# adc.net
KiCad netlist of a schematic drawn in Altium Designer
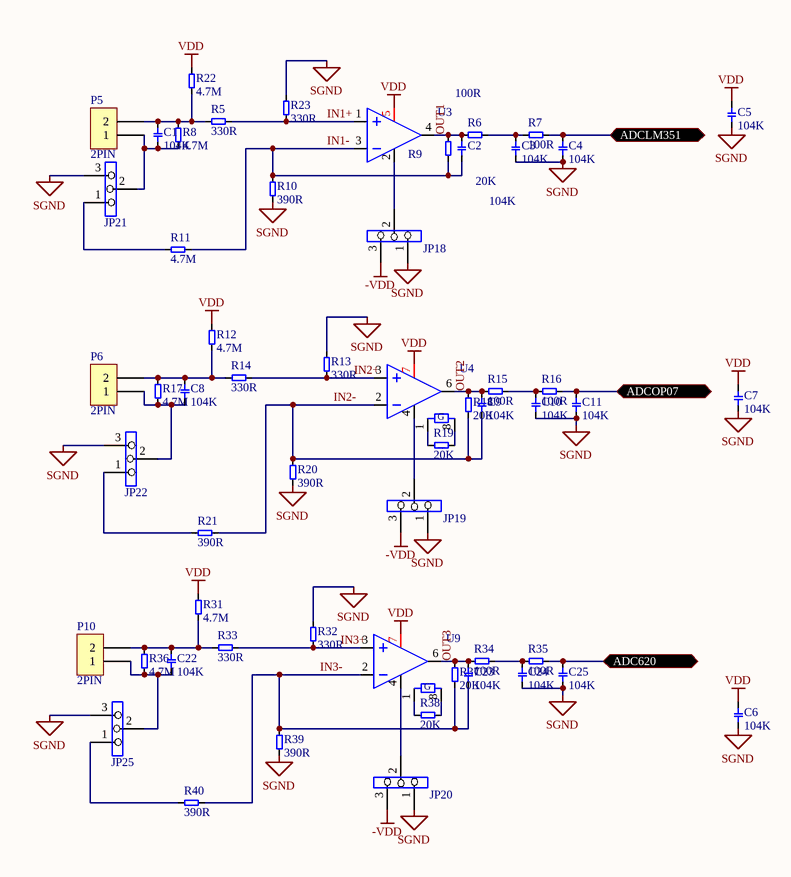
[diagram p0: adc.SchDoc]

(export (version "E")
  (design (tool "Eeschema 10.0.6"))
  (components
    (comp (ref "C1")
      (value "104K")
      (footprint "0603")
      (description "电容")
      (fields (field (name "PUBLISHER") "Altium Limited"))
      (libsource (lib "Miscellaneous Devices") (part "Cap"))
    )
    (comp (ref "C2")
      (value "104K")
      (footprint "0603")
      (description "电容")
      (fields (field (name "PUBLISHER") "Altium Limited"))
      (libsource (lib "Miscellaneous Devices") (part "Cap"))
    )
    (comp (ref "C3")
      (value "104K")
      (footprint "0603")
      (description "电容")
      (fields (field (name "PUBLISHER") "Altium Limited"))
      (libsource (lib "Miscellaneous Devices") (part "Cap"))
    )
    (comp (ref "C4")
      (value "104K")
      (footprint "0603")
      (description "电容")
      (fields (field (name "PUBLISHER") "Altium Limited"))
      (libsource (lib "Miscellaneous Devices") (part "Cap"))
    )
    (comp (ref "C5")
      (value "104K")
      (footprint "0603")
      (description "电容")
      (fields (field (name "PUBLISHER") "Altium Limited"))
      (libsource (lib "Miscellaneous Devices") (part "Cap"))
    )
    (comp (ref "C6")
      (value "104K")
      (footprint "0603")
      (description "电容")
      (fields (field (name "PUBLISHER") "Altium Limited"))
      (libsource (lib "Miscellaneous Devices") (part "Cap"))
    )
    (comp (ref "C7")
      (value "104K")
      (footprint "0603")
      (description "电容")
      (fields (field (name "PUBLISHER") "Altium Limited"))
      (libsource (lib "Miscellaneous Devices") (part "Cap"))
    )
    (comp (ref "C8")
      (value "104K")
      (footprint "0603")
      (description "电容")
      (fields (field (name "PUBLISHER") "Altium Limited"))
      (libsource (lib "Miscellaneous Devices") (part "Cap"))
    )
    (comp (ref "C9")
      (value "104K")
      (footprint "0603")
      (description "电容")
      (fields (field (name "PUBLISHER") "Altium Limited"))
      (libsource (lib "Miscellaneous Devices") (part "Cap"))
    )
    (comp (ref "C10")
      (value "104K")
      (footprint "0603")
      (description "电容")
      (fields (field (name "PUBLISHER") "Altium Limited"))
      (libsource (lib "Miscellaneous Devices") (part "Cap"))
    )
    (comp (ref "C11")
      (value "104K")
      (footprint "0603")
      (description "电容")
      (fields (field (name "PUBLISHER") "Altium Limited"))
      (libsource (lib "Miscellaneous Devices") (part "Cap"))
    )
    (comp (ref "C22")
      (value "104K")
      (footprint "0603")
      (description "电容")
      (fields (field (name "PUBLISHER") "Altium Limited"))
      (libsource (lib "Miscellaneous Devices") (part "Cap"))
    )
    (comp (ref "C23")
      (value "104K")
      (footprint "0603")
      (description "电容")
      (fields (field (name "PUBLISHER") "Altium Limited"))
      (libsource (lib "Miscellaneous Devices") (part "Cap"))
    )
    (comp (ref "C24")
      (value "104K")
      (footprint "0603")
      (description "电容")
      (fields (field (name "PUBLISHER") "Altium Limited"))
      (libsource (lib "Miscellaneous Devices") (part "Cap"))
    )
    (comp (ref "C25")
      (value "104K")
      (footprint "0603")
      (description "电容")
      (fields (field (name "PUBLISHER") "Altium Limited"))
      (libsource (lib "Miscellaneous Devices") (part "Cap"))
    )
    (comp (ref "JP18")
      (value "Jumper3")
      (footprint "CON3-P2.54")
      (libsource (lib "Miscellaneous Connectors") (part "Jumper3"))
    )
    (comp (ref "JP19")
      (value "Jumper3")
      (footprint "CON3-P2.54")
      (libsource (lib "Miscellaneous Connectors") (part "Jumper3"))
    )
    (comp (ref "JP20")
      (value "Jumper3")
      (footprint "CON3-P2.54")
      (libsource (lib "Miscellaneous Connectors") (part "Jumper3"))
    )
    (comp (ref "JP21")
      (value "Jumper3")
      (footprint "CON3-P2.54")
      (libsource (lib "Miscellaneous Connectors") (part "Jumper3"))
    )
    (comp (ref "JP22")
      (value "Jumper3")
      (footprint "CON3-P2.54")
      (libsource (lib "Miscellaneous Connectors") (part "Jumper3"))
    )
    (comp (ref "JP25")
      (value "Jumper3")
      (footprint "CON3-P2.54")
      (libsource (lib "Miscellaneous Connectors") (part "Jumper3"))
    )
    (comp (ref "P5")
      (value "2PIN")
      (footprint "CON2-P2.54")
      (description "连接器")
      (fields (field (name "PUBLISHER") "Altium Limited"))
      (libsource (lib "Miscellaneous Connectors") (part "Header 2"))
    )
    (comp (ref "P6")
      (value "2PIN")
      (footprint "CON2-P2.54")
      (description "连接器")
      (fields (field (name "PUBLISHER") "Altium Limited"))
      (libsource (lib "Miscellaneous Connectors") (part "Header 2"))
    )
    (comp (ref "P10")
      (value "2PIN")
      (footprint "CON2-P2.54")
      (description "连接器")
      (fields (field (name "PUBLISHER") "Altium Limited"))
      (libsource (lib "Miscellaneous Connectors") (part "Header 2"))
    )
    (comp (ref "R5")
      (value "330R")
      (footprint "0603")
      (description "电阻")
      (fields (field (name "PUBLISHER") "Altium Limited"))
      (libsource (lib "Miscellaneous Devices") (part "Res1"))
    )
    (comp (ref "R6")
      (value "100R")
      (footprint "0603")
      (description "电阻")
      (fields (field (name "PUBLISHER") "Altium Limited"))
      (libsource (lib "Miscellaneous Devices") (part "Res1"))
    )
    (comp (ref "R7")
      (value "100R")
      (footprint "0603")
      (description "电阻")
      (fields (field (name "PUBLISHER") "Altium Limited"))
      (libsource (lib "Miscellaneous Devices") (part "Res1"))
    )
    (comp (ref "R8")
      (value "4.7M")
      (footprint "0603")
      (description "电阻")
      (fields (field (name "PUBLISHER") "Altium Limited"))
      (libsource (lib "Miscellaneous Devices") (part "Res1"))
    )
    (comp (ref "R9")
      (value "20K")
      (footprint "0603")
      (description "电阻")
      (fields (field (name "PUBLISHER") "Altium Limited"))
      (libsource (lib "Miscellaneous Devices") (part "Res1"))
    )
    (comp (ref "R10")
      (value "390R")
      (footprint "0603")
      (description "电阻")
      (fields (field (name "PUBLISHER") "Altium Limited"))
      (libsource (lib "Miscellaneous Devices") (part "Res1"))
    )
    (comp (ref "R11")
      (value "4.7M")
      (footprint "0603")
      (description "电阻")
      (fields (field (name "PUBLISHER") "Altium Limited"))
      (libsource (lib "Miscellaneous Devices") (part "Res1"))
    )
    (comp (ref "R12")
      (value "4.7M")
      (footprint "0603")
      (description "电阻")
      (fields (field (name "PUBLISHER") "Altium Limited"))
      (libsource (lib "Miscellaneous Devices") (part "Res1"))
    )
    (comp (ref "R13")
      (value "330R")
      (footprint "0603")
      (description "电阻")
      (fields (field (name "PUBLISHER") "Altium Limited"))
      (libsource (lib "Miscellaneous Devices") (part "Res1"))
    )
    (comp (ref "R14")
      (value "330R")
      (footprint "0603")
      (description "电阻")
      (fields (field (name "PUBLISHER") "Altium Limited"))
      (libsource (lib "Miscellaneous Devices") (part "Res1"))
    )
    (comp (ref "R15")
      (value "100R")
      (footprint "0603")
      (description "电阻")
      (fields (field (name "PUBLISHER") "Altium Limited"))
      (libsource (lib "Miscellaneous Devices") (part "Res1"))
    )
    (comp (ref "R16")
      (value "100R")
      (footprint "0603")
      (description "电阻")
      (fields (field (name "PUBLISHER") "Altium Limited"))
      (libsource (lib "Miscellaneous Devices") (part "Res1"))
    )
    (comp (ref "R17")
      (value "4.7M")
      (footprint "0603")
      (description "电阻")
      (fields (field (name "PUBLISHER") "Altium Limited"))
      (libsource (lib "Miscellaneous Devices") (part "Res1"))
    )
    (comp (ref "R18")
      (value "20K")
      (footprint "0603")
      (description "电阻")
      (fields (field (name "PUBLISHER") "Altium Limited"))
      (libsource (lib "Miscellaneous Devices") (part "Res1"))
    )
    (comp (ref "R19")
      (value "20K")
      (footprint "0603")
      (description "电阻")
      (fields (field (name "PUBLISHER") "Altium Limited"))
      (libsource (lib "Miscellaneous Devices") (part "Res1"))
    )
    (comp (ref "R20")
      (value "390R")
      (footprint "0603")
      (description "电阻")
      (fields (field (name "PUBLISHER") "Altium Limited"))
      (libsource (lib "Miscellaneous Devices") (part "Res1"))
    )
    (comp (ref "R21")
      (value "390R")
      (footprint "0603")
      (description "电阻")
      (fields (field (name "PUBLISHER") "Altium Limited"))
      (libsource (lib "Miscellaneous Devices") (part "Res1"))
    )
    (comp (ref "R22")
      (value "4.7M")
      (footprint "0603")
      (description "电阻")
      (fields (field (name "PUBLISHER") "Altium Limited"))
      (libsource (lib "Miscellaneous Devices") (part "Res1"))
    )
    (comp (ref "R23")
      (value "330R")
      (footprint "0603")
      (description "电阻")
      (fields (field (name "PUBLISHER") "Altium Limited"))
      (libsource (lib "Miscellaneous Devices") (part "Res1"))
    )
    (comp (ref "R31")
      (value "4.7M")
      (footprint "0603")
      (description "电阻")
      (fields (field (name "PUBLISHER") "Altium Limited"))
      (libsource (lib "Miscellaneous Devices") (part "Res1"))
    )
    (comp (ref "R32")
      (value "330R")
      (footprint "0603")
      (description "电阻")
      (fields (field (name "PUBLISHER") "Altium Limited"))
      (libsource (lib "Miscellaneous Devices") (part "Res1"))
    )
    (comp (ref "R33")
      (value "330R")
      (footprint "0603")
      (description "电阻")
      (fields (field (name "PUBLISHER") "Altium Limited"))
      (libsource (lib "Miscellaneous Devices") (part "Res1"))
    )
    (comp (ref "R34")
      (value "100R")
      (footprint "0603")
      (description "电阻")
      (fields (field (name "PUBLISHER") "Altium Limited"))
      (libsource (lib "Miscellaneous Devices") (part "Res1"))
    )
    (comp (ref "R35")
      (value "100R")
      (footprint "0603")
      (description "电阻")
      (fields (field (name "PUBLISHER") "Altium Limited"))
      (libsource (lib "Miscellaneous Devices") (part "Res1"))
    )
    (comp (ref "R36")
      (value "4.7M")
      (footprint "0603")
      (description "电阻")
      (fields (field (name "PUBLISHER") "Altium Limited"))
      (libsource (lib "Miscellaneous Devices") (part "Res1"))
    )
    (comp (ref "R37")
      (value "20K")
      (footprint "0603")
      (description "电阻")
      (fields (field (name "PUBLISHER") "Altium Limited"))
      (libsource (lib "Miscellaneous Devices") (part "Res1"))
    )
    (comp (ref "R38")
      (value "20K")
      (footprint "0603")
      (description "电阻")
      (fields (field (name "PUBLISHER") "Altium Limited"))
      (libsource (lib "Miscellaneous Devices") (part "Res1"))
    )
    (comp (ref "R39")
      (value "390R")
      (footprint "0603")
      (description "电阻")
      (fields (field (name "PUBLISHER") "Altium Limited"))
      (libsource (lib "Miscellaneous Devices") (part "Res1"))
    )
    (comp (ref "R40")
      (value "390R")
      (footprint "0603")
      (description "电阻")
      (fields (field (name "PUBLISHER") "Altium Limited"))
      (libsource (lib "Miscellaneous Devices") (part "Res1"))
    )
    (comp (ref "U3")
      (value "LM321")
      (footprint "SOT-23-5L")
      (description "运放")
      (libsource (lib "Miscellaneous Devices") (part "LM321"))
    )
    (comp (ref "U4")
      (value "OP07")
      (footprint "SOIC8_39MM")
      (description "运放")
      (libsource (lib "Miscellaneous Devices") (part "AD620"))
    )
    (comp (ref "U9")
      (value "OP07")
      (footprint "SOIC8_39MM")
      (description "运放")
      (libsource (lib "Miscellaneous Devices") (part "AD620"))
    )
  )
  (nets
    (net (code "1") (name "-VDD") (class "Default")
      (node (ref "JP18") (pin "3") (pintype "passive"))
      (node (ref "JP19") (pin "3") (pintype "passive"))
      (node (ref "JP20") (pin "3") (pintype "passive"))
    )
    (net (code "2") (name "/ADC620") (class "Default")
      (node (ref "C25") (pin "2") (pinfunction "2_2") (pintype "passive"))
      (node (ref "R35") (pin "1") (pinfunction "1_1") (pintype "passive"))
    )
    (net (code "3") (name "/ADCLM351") (class "Default")
      (node (ref "C4") (pin "2") (pinfunction "2_2") (pintype "passive"))
      (node (ref "R7") (pin "1") (pinfunction "1_1") (pintype "passive"))
    )
    (net (code "4") (name "/ADCOP07") (class "Default")
      (node (ref "C11") (pin "2") (pinfunction "2_2") (pintype "passive"))
      (node (ref "R16") (pin "1") (pinfunction "1_1") (pintype "passive"))
    )
    (net (code "5") (name "/IN1+") (class "Default")
      (node (ref "R23") (pin "1") (pinfunction "1_1") (pintype "passive"))
      (node (ref "R5") (pin "2") (pinfunction "2_2") (pintype "passive"))
      (node (ref "U3") (pin "1") (pinfunction "IN1+_1") (pintype "passive"))
    )
    (net (code "6") (name "/IN1-") (class "Default")
      (node (ref "C2") (pin "1") (pinfunction "1_1") (pintype "passive"))
      (node (ref "R10") (pin "1") (pinfunction "1_1") (pintype "passive"))
      (node (ref "R11") (pin "1") (pinfunction "1_1") (pintype "passive"))
      (node (ref "R9") (pin "2") (pinfunction "2_2") (pintype "passive"))
      (node (ref "U3") (pin "3") (pinfunction "IN1-_3") (pintype "passive"))
    )
    (net (code "7") (name "/IN2+") (class "Default")
      (node (ref "R13") (pin "1") (pinfunction "1_1") (pintype "passive"))
      (node (ref "R14") (pin "2") (pinfunction "2_2") (pintype "passive"))
      (node (ref "U4") (pin "3") (pinfunction "IN1+_3") (pintype "passive"))
    )
    (net (code "8") (name "/IN2-") (class "Default")
      (node (ref "C9") (pin "1") (pinfunction "1_1") (pintype "passive"))
      (node (ref "R18") (pin "2") (pinfunction "2_2") (pintype "passive"))
      (node (ref "R20") (pin "1") (pinfunction "1_1") (pintype "passive"))
      (node (ref "R21") (pin "2") (pinfunction "2_2") (pintype "passive"))
      (node (ref "U4") (pin "2") (pinfunction "IN1-_2") (pintype "passive"))
    )
    (net (code "9") (name "/IN3+") (class "Default")
      (node (ref "R32") (pin "1") (pinfunction "1_1") (pintype "passive"))
      (node (ref "R33") (pin "2") (pinfunction "2_2") (pintype "passive"))
      (node (ref "U9") (pin "3") (pinfunction "IN1+_3") (pintype "passive"))
    )
    (net (code "10") (name "/IN3-") (class "Default")
      (node (ref "C23") (pin "1") (pinfunction "1_1") (pintype "passive"))
      (node (ref "R37") (pin "2") (pinfunction "2_2") (pintype "passive"))
      (node (ref "R39") (pin "1") (pinfunction "1_1") (pintype "passive"))
      (node (ref "R40") (pin "2") (pinfunction "2_2") (pintype "passive"))
      (node (ref "U9") (pin "2") (pinfunction "IN1-_2") (pintype "passive"))
    )
    (net (code "11") (name "/OUT1") (class "Default")
      (node (ref "C2") (pin "2") (pinfunction "2_2") (pintype "passive"))
      (node (ref "R6") (pin "2") (pinfunction "2_2") (pintype "passive"))
      (node (ref "R9") (pin "1") (pinfunction "1_1") (pintype "passive"))
      (node (ref "U3") (pin "4") (pinfunction "OUT1_4") (pintype "passive"))
    )
    (net (code "12") (name "/OUT2") (class "Default")
      (node (ref "C9") (pin "2") (pinfunction "2_2") (pintype "passive"))
      (node (ref "R15") (pin "2") (pinfunction "2_2") (pintype "passive"))
      (node (ref "R18") (pin "1") (pinfunction "1_1") (pintype "passive"))
      (node (ref "U4") (pin "6") (pinfunction "OUT1_6") (pintype "passive"))
    )
    (net (code "13") (name "/OUT3") (class "Default")
      (node (ref "C23") (pin "2") (pinfunction "2_2") (pintype "passive"))
      (node (ref "R34") (pin "2") (pinfunction "2_2") (pintype "passive"))
      (node (ref "R37") (pin "1") (pinfunction "1_1") (pintype "passive"))
      (node (ref "U9") (pin "6") (pinfunction "OUT1_6") (pintype "passive"))
    )
    (net (code "14") (name "Net-(C1-Pad1)") (class "Default")
      (node (ref "C1") (pin "1") (pinfunction "1_1") (pintype "passive"))
      (node (ref "JP21") (pin "2") (pintype "passive"))
      (node (ref "P5") (pin "1") (pinfunction "1_1") (pintype "passive"))
      (node (ref "R8") (pin "2") (pinfunction "2_2") (pintype "passive"))
    )
    (net (code "15") (name "Net-(C1-Pad2)") (class "Default")
      (node (ref "C1") (pin "2") (pinfunction "2_2") (pintype "passive"))
      (node (ref "P5") (pin "2") (pinfunction "2_2") (pintype "passive"))
      (node (ref "R22") (pin "2") (pinfunction "2_2") (pintype "passive"))
      (node (ref "R5") (pin "1") (pinfunction "1_1") (pintype "passive"))
      (node (ref "R8") (pin "1") (pinfunction "1_1") (pintype "passive"))
    )
    (net (code "16") (name "Net-(C3-Pad2)") (class "Default")
      (node (ref "C3") (pin "2") (pinfunction "2_2") (pintype "passive"))
      (node (ref "R6") (pin "1") (pinfunction "1_1") (pintype "passive"))
      (node (ref "R7") (pin "2") (pinfunction "2_2") (pintype "passive"))
    )
    (net (code "17") (name "Net-(C8-Pad1)") (class "Default")
      (node (ref "C8") (pin "1") (pinfunction "1_1") (pintype "passive"))
      (node (ref "JP22") (pin "2") (pintype "passive"))
      (node (ref "P6") (pin "1") (pinfunction "1_1") (pintype "passive"))
      (node (ref "R17") (pin "2") (pinfunction "2_2") (pintype "passive"))
    )
    (net (code "18") (name "Net-(C8-Pad2)") (class "Default")
      (node (ref "C8") (pin "2") (pinfunction "2_2") (pintype "passive"))
      (node (ref "P6") (pin "2") (pinfunction "2_2") (pintype "passive"))
      (node (ref "R12") (pin "2") (pinfunction "2_2") (pintype "passive"))
      (node (ref "R14") (pin "1") (pinfunction "1_1") (pintype "passive"))
      (node (ref "R17") (pin "1") (pinfunction "1_1") (pintype "passive"))
    )
    (net (code "19") (name "Net-(C10-Pad2)") (class "Default")
      (node (ref "C10") (pin "2") (pinfunction "2_2") (pintype "passive"))
      (node (ref "R15") (pin "1") (pinfunction "1_1") (pintype "passive"))
      (node (ref "R16") (pin "2") (pinfunction "2_2") (pintype "passive"))
    )
    (net (code "20") (name "Net-(C22-Pad1)") (class "Default")
      (node (ref "C22") (pin "1") (pinfunction "1_1") (pintype "passive"))
      (node (ref "JP25") (pin "2") (pintype "passive"))
      (node (ref "P10") (pin "1") (pinfunction "1_1") (pintype "passive"))
      (node (ref "R36") (pin "2") (pinfunction "2_2") (pintype "passive"))
    )
    (net (code "21") (name "Net-(C22-Pad2)") (class "Default")
      (node (ref "C22") (pin "2") (pinfunction "2_2") (pintype "passive"))
      (node (ref "P10") (pin "2") (pinfunction "2_2") (pintype "passive"))
      (node (ref "R31") (pin "2") (pinfunction "2_2") (pintype "passive"))
      (node (ref "R33") (pin "1") (pinfunction "1_1") (pintype "passive"))
      (node (ref "R36") (pin "1") (pinfunction "1_1") (pintype "passive"))
    )
    (net (code "22") (name "Net-(C24-Pad2)") (class "Default")
      (node (ref "C24") (pin "2") (pinfunction "2_2") (pintype "passive"))
      (node (ref "R34") (pin "1") (pinfunction "1_1") (pintype "passive"))
      (node (ref "R35") (pin "2") (pinfunction "2_2") (pintype "passive"))
    )
    (net (code "23") (name "Net-(JP21-Pad1)") (class "Default")
      (node (ref "JP21") (pin "1") (pintype "passive"))
      (node (ref "R11") (pin "2") (pinfunction "2_2") (pintype "passive"))
    )
    (net (code "24") (name "Net-(JP22-Pad1)") (class "Default")
      (node (ref "JP22") (pin "1") (pintype "passive"))
      (node (ref "R21") (pin "1") (pinfunction "1_1") (pintype "passive"))
    )
    (net (code "25") (name "Net-(JP25-Pad1)") (class "Default")
      (node (ref "JP25") (pin "1") (pintype "passive"))
      (node (ref "R40") (pin "1") (pinfunction "1_1") (pintype "passive"))
    )
    (net (code "26") (name "Net-(R19-Pad1)") (class "Default")
      (node (ref "R19") (pin "1") (pinfunction "1_1") (pintype "passive"))
      (node (ref "U4") (pin "1") (pinfunction "RG_1") (pintype "passive"))
    )
    (net (code "27") (name "Net-(R19-Pad2)") (class "Default")
      (node (ref "R19") (pin "2") (pinfunction "2_2") (pintype "passive"))
      (node (ref "U4") (pin "8") (pinfunction "RG_8") (pintype "passive"))
    )
    (net (code "28") (name "Net-(R38-Pad1)") (class "Default")
      (node (ref "R38") (pin "1") (pinfunction "1_1") (pintype "passive"))
      (node (ref "U9") (pin "1") (pinfunction "RG_1") (pintype "passive"))
    )
    (net (code "29") (name "Net-(R38-Pad2)") (class "Default")
      (node (ref "R38") (pin "2") (pinfunction "2_2") (pintype "passive"))
      (node (ref "U9") (pin "8") (pinfunction "RG_8") (pintype "passive"))
    )
    (net (code "30") (name "Net-(U3-V-)") (class "Default")
      (node (ref "JP18") (pin "2") (pintype "passive"))
      (node (ref "U3") (pin "2") (pinfunction "V-_2") (pintype "power_in"))
    )
    (net (code "31") (name "Net-(U4-V-)") (class "Default")
      (node (ref "JP19") (pin "2") (pintype "passive"))
      (node (ref "U4") (pin "4") (pinfunction "V-_4") (pintype "power_in"))
    )
    (net (code "32") (name "Net-(U9-V-)") (class "Default")
      (node (ref "JP20") (pin "2") (pintype "passive"))
      (node (ref "U9") (pin "4") (pinfunction "V-_4") (pintype "power_in"))
    )
    (net (code "33") (name "SGND") (class "Default")
      (node (ref "C10") (pin "1") (pinfunction "1_1") (pintype "passive"))
      (node (ref "C11") (pin "1") (pinfunction "1_1") (pintype "passive"))
      (node (ref "C24") (pin "1") (pinfunction "1_1") (pintype "passive"))
      (node (ref "C25") (pin "1") (pinfunction "1_1") (pintype "passive"))
      (node (ref "C3") (pin "1") (pinfunction "1_1") (pintype "passive"))
      (node (ref "C4") (pin "1") (pinfunction "1_1") (pintype "passive"))
      (node (ref "C5") (pin "1") (pinfunction "1_1") (pintype "passive"))
      (node (ref "C6") (pin "1") (pinfunction "1_1") (pintype "passive"))
      (node (ref "C7") (pin "1") (pinfunction "1_1") (pintype "passive"))
      (node (ref "JP18") (pin "1") (pintype "passive"))
      (node (ref "JP19") (pin "1") (pintype "passive"))
      (node (ref "JP20") (pin "1") (pintype "passive"))
      (node (ref "JP21") (pin "3") (pintype "passive"))
      (node (ref "JP22") (pin "3") (pintype "passive"))
      (node (ref "JP25") (pin "3") (pintype "passive"))
      (node (ref "R10") (pin "2") (pinfunction "2_2") (pintype "passive"))
      (node (ref "R13") (pin "2") (pinfunction "2_2") (pintype "passive"))
      (node (ref "R20") (pin "2") (pinfunction "2_2") (pintype "passive"))
      (node (ref "R23") (pin "2") (pinfunction "2_2") (pintype "passive"))
      (node (ref "R32") (pin "2") (pinfunction "2_2") (pintype "passive"))
      (node (ref "R39") (pin "2") (pinfunction "2_2") (pintype "passive"))
    )
    (net (code "34") (name "VDD") (class "Default")
      (node (ref "C5") (pin "2") (pinfunction "2_2") (pintype "passive"))
      (node (ref "C6") (pin "2") (pinfunction "2_2") (pintype "passive"))
      (node (ref "C7") (pin "2") (pinfunction "2_2") (pintype "passive"))
      (node (ref "R12") (pin "1") (pinfunction "1_1") (pintype "passive"))
      (node (ref "R22") (pin "1") (pinfunction "1_1") (pintype "passive"))
      (node (ref "R31") (pin "1") (pinfunction "1_1") (pintype "passive"))
      (node (ref "U3") (pin "5") (pinfunction "V+_5") (pintype "power_in"))
      (node (ref "U4") (pin "7") (pinfunction "V+_7") (pintype "power_in"))
      (node (ref "U9") (pin "7") (pinfunction "V+_7") (pintype "power_in"))
    )
  )
)
